# power.net
KiCad netlist of a schematic drawn in Altium Designer
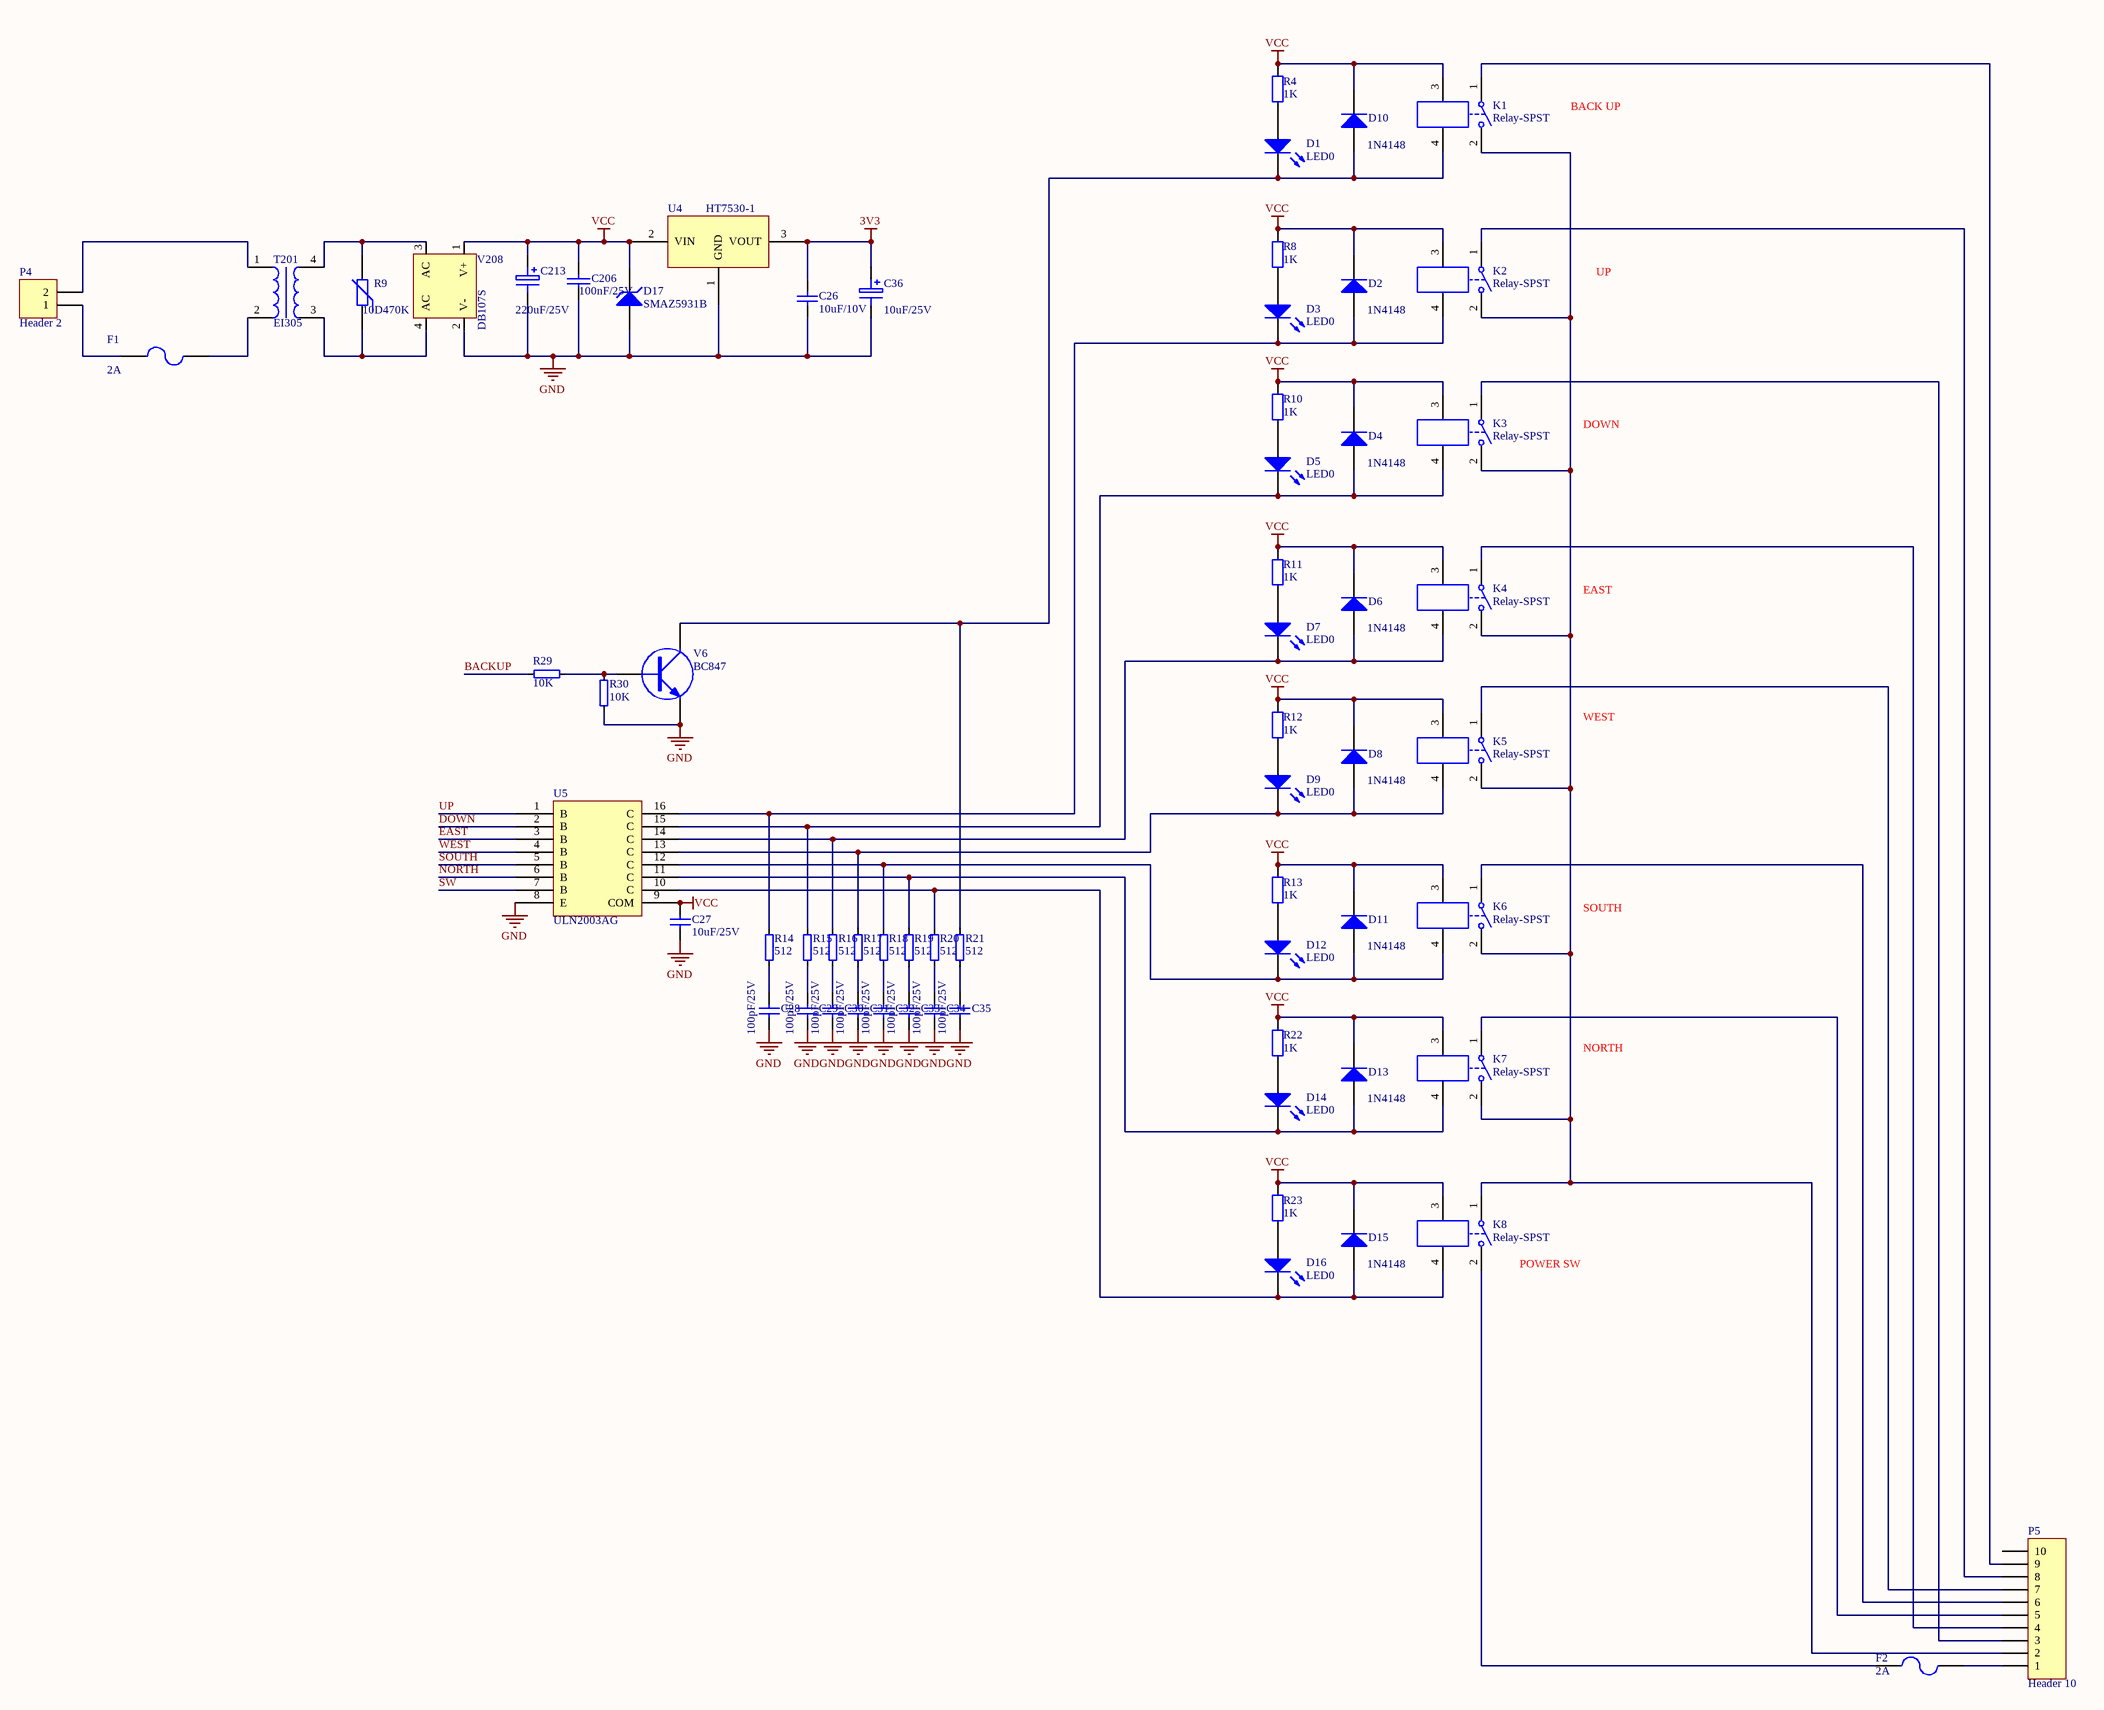
[diagram p0: power.SchDoc]

(export (version "E")
  (design (tool "Eeschema 10.0.6"))
  (components
    (comp (ref "C26")
      (value "10uF/10V")
      (footprint "0603C")
      (description "Capacitor")
      (fields (field (name "PUBLISHER") "Altium Limited"))
      (libsource (lib "Miscellaneous Devices") (part "Cap"))
    )
    (comp (ref "C27")
      (value "10uF/25V")
      (description "Capacitor")
      (fields (field (name "PUBLISHER") "Altium Limited"))
      (libsource (lib "Miscellaneous Devices") (part "Cap"))
    )
    (comp (ref "C28")
      (value "100pF/25V")
      (description "Capacitor")
      (fields (field (name "PUBLISHER") "Altium Limited"))
      (libsource (lib "Miscellaneous Devices") (part "Cap"))
    )
    (comp (ref "C29")
      (value "100pF/25V")
      (description "Capacitor")
      (fields (field (name "PUBLISHER") "Altium Limited"))
      (libsource (lib "Miscellaneous Devices") (part "Cap"))
    )
    (comp (ref "C30")
      (value "100pF/25V")
      (description "Capacitor")
      (fields (field (name "PUBLISHER") "Altium Limited"))
      (libsource (lib "Miscellaneous Devices") (part "Cap"))
    )
    (comp (ref "C31")
      (value "100pF/25V")
      (description "Capacitor")
      (fields (field (name "PUBLISHER") "Altium Limited"))
      (libsource (lib "Miscellaneous Devices") (part "Cap"))
    )
    (comp (ref "C32")
      (value "100pF/25V")
      (description "Capacitor")
      (fields (field (name "PUBLISHER") "Altium Limited"))
      (libsource (lib "Miscellaneous Devices") (part "Cap"))
    )
    (comp (ref "C33")
      (value "100pF/25V")
      (description "Capacitor")
      (fields (field (name "PUBLISHER") "Altium Limited"))
      (libsource (lib "Miscellaneous Devices") (part "Cap"))
    )
    (comp (ref "C34")
      (value "100pF/25V")
      (description "Capacitor")
      (fields (field (name "PUBLISHER") "Altium Limited"))
      (libsource (lib "Miscellaneous Devices") (part "Cap"))
    )
    (comp (ref "C35")
      (value "100pF/25V")
      (description "Capacitor")
      (fields (field (name "PUBLISHER") "Altium Limited"))
      (libsource (lib "Miscellaneous Devices") (part "Cap"))
    )
    (comp (ref "C36")
      (value "10uF/25V")
      (description "Electrolytic Capacitor")
      (libsource (lib "*") (part "ELECTRO1"))
    )
    (comp (ref "C206") (value "100nF/25V") (description "Capacitor") (libsource (lib "*") (part "CAP")))
    (comp (ref "C213")
      (value "220uF/25V")
      (description "Electrolytic Capacitor")
      (libsource (lib "*") (part "ELECTRO1"))
    )
    (comp (ref "D1")
      (value "LED0")
      (footprint "0603led")
      (description "Typical INFRARED GaAs LED")
      (fields (field (name "PUBLISHER") "Altium Limited"))
      (libsource (lib "Miscellaneous Devices") (part "LED0"))
    )
    (comp (ref "D2")
      (value "1N4148")
      (footprint "2017MAIN - BOM:SMD-D")
      (description "Default Diode")
      (fields (field (name "PUBLISHER") "Altium Limited"))
      (libsource (lib "Miscellaneous Devices") (part "Diode"))
    )
    (comp (ref "D3")
      (value "LED0")
      (footprint "0603led")
      (description "Typical INFRARED GaAs LED")
      (fields (field (name "PUBLISHER") "Altium Limited"))
      (libsource (lib "Miscellaneous Devices") (part "LED0"))
    )
    (comp (ref "D4")
      (value "1N4148")
      (footprint "2017MAIN - BOM:SMD-D")
      (description "Default Diode")
      (fields (field (name "PUBLISHER") "Altium Limited"))
      (libsource (lib "Miscellaneous Devices") (part "Diode"))
    )
    (comp (ref "D5")
      (value "LED0")
      (footprint "0603led")
      (description "Typical INFRARED GaAs LED")
      (fields (field (name "PUBLISHER") "Altium Limited"))
      (libsource (lib "Miscellaneous Devices") (part "LED0"))
    )
    (comp (ref "D6")
      (value "1N4148")
      (footprint "2017MAIN - BOM:SMD-D")
      (description "Default Diode")
      (fields (field (name "PUBLISHER") "Altium Limited"))
      (libsource (lib "Miscellaneous Devices") (part "Diode"))
    )
    (comp (ref "D7")
      (value "LED0")
      (footprint "0603led")
      (description "Typical INFRARED GaAs LED")
      (fields (field (name "PUBLISHER") "Altium Limited"))
      (libsource (lib "Miscellaneous Devices") (part "LED0"))
    )
    (comp (ref "D8")
      (value "1N4148")
      (footprint "2017MAIN - BOM:SMD-D")
      (description "Default Diode")
      (fields (field (name "PUBLISHER") "Altium Limited"))
      (libsource (lib "Miscellaneous Devices") (part "Diode"))
    )
    (comp (ref "D9")
      (value "LED0")
      (footprint "0603led")
      (description "Typical INFRARED GaAs LED")
      (fields (field (name "PUBLISHER") "Altium Limited"))
      (libsource (lib "Miscellaneous Devices") (part "LED0"))
    )
    (comp (ref "D10")
      (value "1N4148")
      (footprint "2017MAIN - BOM:SMD-D")
      (description "Default Diode")
      (fields (field (name "PUBLISHER") "Altium Limited"))
      (libsource (lib "Miscellaneous Devices") (part "Diode"))
    )
    (comp (ref "D11")
      (value "1N4148")
      (footprint "2017MAIN - BOM:SMD-D")
      (description "Default Diode")
      (fields (field (name "PUBLISHER") "Altium Limited"))
      (libsource (lib "Miscellaneous Devices") (part "Diode"))
    )
    (comp (ref "D12")
      (value "LED0")
      (footprint "0603led")
      (description "Typical INFRARED GaAs LED")
      (fields (field (name "PUBLISHER") "Altium Limited"))
      (libsource (lib "Miscellaneous Devices") (part "LED0"))
    )
    (comp (ref "D13")
      (value "1N4148")
      (footprint "2017MAIN - BOM:SMD-D")
      (description "Default Diode")
      (fields (field (name "PUBLISHER") "Altium Limited"))
      (libsource (lib "Miscellaneous Devices") (part "Diode"))
    )
    (comp (ref "D14")
      (value "LED0")
      (footprint "0603led")
      (description "Typical INFRARED GaAs LED")
      (fields (field (name "PUBLISHER") "Altium Limited"))
      (libsource (lib "Miscellaneous Devices") (part "LED0"))
    )
    (comp (ref "D15")
      (value "1N4148")
      (footprint "2017MAIN - BOM:SMD-D")
      (description "Default Diode")
      (fields (field (name "PUBLISHER") "Altium Limited"))
      (libsource (lib "Miscellaneous Devices") (part "Diode"))
    )
    (comp (ref "D16")
      (value "LED0")
      (footprint "0603led")
      (description "Typical INFRARED GaAs LED")
      (fields (field (name "PUBLISHER") "Altium Limited"))
      (libsource (lib "Miscellaneous Devices") (part "LED0"))
    )
    (comp (ref "D17")
      (value "SMAZ5931B")
      (footprint "SMA")
      (description "Zener Diode")
      (fields (field (name "PUBLISHER") "Altium Limited"))
      (libsource (lib "Miscellaneous Devices") (part "D Zener"))
    )
    (comp (ref "F1")
      (value "2A")
      (footprint "2017MAIN - BOM:FU")
      (description "Fuse")
      (fields (field (name "PUBLISHER") "Altium Limited"))
      (libsource (lib "Miscellaneous Devices") (part "Fuse 2"))
    )
    (comp (ref "F2")
      (value "2A")
      (footprint "2017MAIN - BOM:FU")
      (description "Fuse")
      (fields (field (name "PUBLISHER") "Altium Limited"))
      (libsource (lib "Miscellaneous Devices") (part "Fuse 2"))
    )
    (comp (ref "K1")
      (value "Relay-SPST")
      (footprint "2017MAIN - BOM:KKK")
      (description "Single-Pole Single-Throw Relay")
      (fields (field (name "PUBLISHER") "Altium Limited"))
      (libsource (lib "Miscellaneous Devices") (part "Relay-SPST"))
    )
    (comp (ref "K2")
      (value "Relay-SPST")
      (footprint "2017MAIN - BOM:KKK")
      (description "Single-Pole Single-Throw Relay")
      (fields (field (name "PUBLISHER") "Altium Limited"))
      (libsource (lib "Miscellaneous Devices") (part "Relay-SPST"))
    )
    (comp (ref "K3")
      (value "Relay-SPST")
      (footprint "2017MAIN - BOM:KKK")
      (description "Single-Pole Single-Throw Relay")
      (fields (field (name "PUBLISHER") "Altium Limited"))
      (libsource (lib "Miscellaneous Devices") (part "Relay-SPST"))
    )
    (comp (ref "K4")
      (value "Relay-SPST")
      (footprint "2017MAIN - BOM:KKK")
      (description "Single-Pole Single-Throw Relay")
      (fields (field (name "PUBLISHER") "Altium Limited"))
      (libsource (lib "Miscellaneous Devices") (part "Relay-SPST"))
    )
    (comp (ref "K5")
      (value "Relay-SPST")
      (footprint "2017MAIN - BOM:KKK")
      (description "Single-Pole Single-Throw Relay")
      (fields (field (name "PUBLISHER") "Altium Limited"))
      (libsource (lib "Miscellaneous Devices") (part "Relay-SPST"))
    )
    (comp (ref "K6")
      (value "Relay-SPST")
      (footprint "2017MAIN - BOM:KKK")
      (description "Single-Pole Single-Throw Relay")
      (fields (field (name "PUBLISHER") "Altium Limited"))
      (libsource (lib "Miscellaneous Devices") (part "Relay-SPST"))
    )
    (comp (ref "K7")
      (value "Relay-SPST")
      (footprint "2017MAIN - BOM:KKK")
      (description "Single-Pole Single-Throw Relay")
      (fields (field (name "PUBLISHER") "Altium Limited"))
      (libsource (lib "Miscellaneous Devices") (part "Relay-SPST"))
    )
    (comp (ref "K8")
      (value "Relay-SPST")
      (footprint "2017MAIN - BOM:KKK")
      (description "Single-Pole Single-Throw Relay")
      (fields (field (name "PUBLISHER") "Altium Limited"))
      (libsource (lib "Miscellaneous Devices") (part "Relay-SPST"))
    )
    (comp (ref "P4")
      (value "Header 2")
      (footprint "2017MAIN - BOM:CH022")
      (description "Header, 2-Pin")
      (fields (field (name "PUBLISHER") "Altium Limited"))
      (libsource (lib "Miscellaneous Connectors") (part "Header 2"))
    )
    (comp (ref "P5")
      (value "Header 10")
      (footprint "2017MAIN - BOM:CN10")
      (description "Header, 10-Pin")
      (fields (field (name "PUBLISHER") "Altium Limited"))
      (libsource (lib "Miscellaneous Connectors") (part "Header 10"))
    )
    (comp (ref "R4")
      (value "1K")
      (footprint "0603R")
      (description "Resistor")
      (fields (field (name "PUBLISHER") "Altium Limited"))
      (libsource (lib "Miscellaneous Devices") (part "Res2"))
    )
    (comp (ref "R8")
      (value "1K")
      (footprint "0603R")
      (description "Resistor")
      (fields (field (name "PUBLISHER") "Altium Limited"))
      (libsource (lib "Miscellaneous Devices") (part "Res2"))
    )
    (comp (ref "R9")
      (value "10D470K")
      (description "Varistor (Voltage-Sensitive Resistor)")
      (fields (field (name "PUBLISHER") "Altium Limited"))
      (libsource (lib "Miscellaneous Devices") (part "Res Varistor"))
    )
    (comp (ref "R10")
      (value "1K")
      (footprint "0603R")
      (description "Resistor")
      (fields (field (name "PUBLISHER") "Altium Limited"))
      (libsource (lib "Miscellaneous Devices") (part "Res2"))
    )
    (comp (ref "R11")
      (value "1K")
      (footprint "0603R")
      (description "Resistor")
      (fields (field (name "PUBLISHER") "Altium Limited"))
      (libsource (lib "Miscellaneous Devices") (part "Res2"))
    )
    (comp (ref "R12")
      (value "1K")
      (footprint "0603R")
      (description "Resistor")
      (fields (field (name "PUBLISHER") "Altium Limited"))
      (libsource (lib "Miscellaneous Devices") (part "Res2"))
    )
    (comp (ref "R13")
      (value "1K")
      (footprint "0603R")
      (description "Resistor")
      (fields (field (name "PUBLISHER") "Altium Limited"))
      (libsource (lib "Miscellaneous Devices") (part "Res2"))
    )
    (comp (ref "R14") (value "512") (footprint "0603R") (libsource (lib "*") (part "RES2")))
    (comp (ref "R15") (value "512") (footprint "0603R") (libsource (lib "*") (part "RES2")))
    (comp (ref "R16") (value "512") (footprint "0603R") (libsource (lib "*") (part "RES2")))
    (comp (ref "R17") (value "512") (footprint "0603R") (libsource (lib "*") (part "RES2")))
    (comp (ref "R18") (value "512") (footprint "0603R") (libsource (lib "*") (part "RES2")))
    (comp (ref "R19") (value "512") (footprint "0603R") (libsource (lib "*") (part "RES2")))
    (comp (ref "R20") (value "512") (footprint "0603R") (libsource (lib "*") (part "RES2")))
    (comp (ref "R21") (value "512") (footprint "0603R") (libsource (lib "*") (part "RES2")))
    (comp (ref "R22")
      (value "1K")
      (footprint "0603R")
      (description "Resistor")
      (fields (field (name "PUBLISHER") "Altium Limited"))
      (libsource (lib "Miscellaneous Devices") (part "Res2"))
    )
    (comp (ref "R23")
      (value "1K")
      (footprint "0603R")
      (description "Resistor")
      (fields (field (name "PUBLISHER") "Altium Limited"))
      (libsource (lib "Miscellaneous Devices") (part "Res2"))
    )
    (comp (ref "R29") (value "10K") (footprint "0603R") (libsource (lib "*") (part "RES2")))
    (comp (ref "R30") (value "10K") (footprint "0603R") (libsource (lib "*") (part "RES2")))
    (comp (ref "T201") (value "EI305") (footprint "2017MAIN - BOM:T01") (libsource (lib "*") (part "EI305")))
    (comp (ref "U4") (value "HT7530-1") (libsource (lib "Schlib_20110825") (part "HT7533-1")))
    (comp (ref "U5") (value "ULN2003AG") (libsource (lib "Schlib_20110825") (part "ULN2003AG")))
    (comp (ref "V6")
      (value "BC847")
      (footprint "SOT-23")
      (description "NPN Transistor")
      (libsource (lib "*") (part "NPN"))
    )
    (comp (ref "V208")
      (value "DB107S")
      (footprint "BRIDGE")
      (description "Diode Bridge")
      (libsource (lib "*") (part "BRIDGE2"))
    )
  )
  (nets
    (net (code "1") (name "/BACKUP") (class "Default")
      (node (ref "R29") (pin "1") (pinfunction "1_1") (pintype "passive"))
    )
    (net (code "2") (name "/DOWN") (class "Default")
      (node (ref "U5") (pin "2") (pinfunction "B_2") (pintype "passive"))
    )
    (net (code "3") (name "/EAST") (class "Default")
      (node (ref "U5") (pin "3") (pinfunction "B_3") (pintype "passive"))
    )
    (net (code "4") (name "/NORTH") (class "Default")
      (node (ref "U5") (pin "6") (pinfunction "B_6") (pintype "passive"))
    )
    (net (code "5") (name "/SOUTH") (class "Default")
      (node (ref "U5") (pin "5") (pinfunction "B_5") (pintype "passive"))
    )
    (net (code "6") (name "/SW") (class "Default")
      (node (ref "U5") (pin "7") (pinfunction "B_7") (pintype "passive"))
    )
    (net (code "7") (name "/UP") (class "Default")
      (node (ref "U5") (pin "1") (pinfunction "B_1") (pintype "passive"))
    )
    (net (code "8") (name "/WEST") (class "Default")
      (node (ref "U5") (pin "4") (pinfunction "B_4") (pintype "passive"))
    )
    (net (code "9") (name "3V3") (class "Default")
      (node (ref "C26") (pin "1") (pinfunction "1_1") (pintype "passive"))
      (node (ref "C36") (pin "1") (pinfunction "1_1") (pintype "passive"))
      (node (ref "U4") (pin "3") (pinfunction "VOUT_3") (pintype "passive"))
    )
    (net (code "10") (name "GND") (class "Default")
      (node (ref "C206") (pin "2") (pinfunction "2_2") (pintype "passive"))
      (node (ref "C213") (pin "2") (pinfunction "2_2") (pintype "passive"))
      (node (ref "C26") (pin "2") (pinfunction "2_2") (pintype "passive"))
      (node (ref "C27") (pin "2") (pinfunction "2_2") (pintype "passive"))
      (node (ref "C28") (pin "2") (pinfunction "2_2") (pintype "passive"))
      (node (ref "C29") (pin "2") (pinfunction "2_2") (pintype "passive"))
      (node (ref "C30") (pin "2") (pinfunction "2_2") (pintype "passive"))
      (node (ref "C31") (pin "2") (pinfunction "2_2") (pintype "passive"))
      (node (ref "C32") (pin "2") (pinfunction "2_2") (pintype "passive"))
      (node (ref "C33") (pin "2") (pinfunction "2_2") (pintype "passive"))
      (node (ref "C34") (pin "2") (pinfunction "2_2") (pintype "passive"))
      (node (ref "C35") (pin "2") (pinfunction "2_2") (pintype "passive"))
      (node (ref "C36") (pin "2") (pinfunction "2_2") (pintype "passive"))
      (node (ref "D17") (pin "1") (pinfunction "A_1") (pintype "passive"))
      (node (ref "R30") (pin "2") (pinfunction "2_2") (pintype "passive"))
      (node (ref "U4") (pin "1") (pinfunction "GND_1") (pintype "passive"))
      (node (ref "U5") (pin "8") (pinfunction "E_8") (pintype "passive"))
      (node (ref "V208") (pin "2") (pinfunction "V-_2") (pintype "passive"))
      (node (ref "V6") (pin "2") (pinfunction "E_2") (pintype "passive"))
    )
    (net (code "11") (name "Net-(C28-Pad1)") (class "Default")
      (node (ref "C28") (pin "1") (pinfunction "1_1") (pintype "passive"))
      (node (ref "R14") (pin "2") (pinfunction "2_2") (pintype "passive"))
    )
    (net (code "12") (name "Net-(C29-Pad1)") (class "Default")
      (node (ref "C29") (pin "1") (pinfunction "1_1") (pintype "passive"))
      (node (ref "R15") (pin "2") (pinfunction "2_2") (pintype "passive"))
    )
    (net (code "13") (name "Net-(C30-Pad1)") (class "Default")
      (node (ref "C30") (pin "1") (pinfunction "1_1") (pintype "passive"))
      (node (ref "R16") (pin "2") (pinfunction "2_2") (pintype "passive"))
    )
    (net (code "14") (name "Net-(C31-Pad1)") (class "Default")
      (node (ref "C31") (pin "1") (pinfunction "1_1") (pintype "passive"))
      (node (ref "R17") (pin "2") (pinfunction "2_2") (pintype "passive"))
    )
    (net (code "15") (name "Net-(C32-Pad1)") (class "Default")
      (node (ref "C32") (pin "1") (pinfunction "1_1") (pintype "passive"))
      (node (ref "R18") (pin "2") (pinfunction "2_2") (pintype "passive"))
    )
    (net (code "16") (name "Net-(C33-Pad1)") (class "Default")
      (node (ref "C33") (pin "1") (pinfunction "1_1") (pintype "passive"))
      (node (ref "R19") (pin "2") (pinfunction "2_2") (pintype "passive"))
    )
    (net (code "17") (name "Net-(C34-Pad1)") (class "Default")
      (node (ref "C34") (pin "1") (pinfunction "1_1") (pintype "passive"))
      (node (ref "R20") (pin "2") (pinfunction "2_2") (pintype "passive"))
    )
    (net (code "18") (name "Net-(C35-Pad1)") (class "Default")
      (node (ref "C35") (pin "1") (pinfunction "1_1") (pintype "passive"))
      (node (ref "R21") (pin "2") (pinfunction "2_2") (pintype "passive"))
    )
    (net (code "19") (name "Net-(D1-A)") (class "Default")
      (node (ref "D1") (pin "1") (pinfunction "A_1") (pintype "passive"))
      (node (ref "R4") (pin "1") (pinfunction "1_1") (pintype "passive"))
    )
    (net (code "20") (name "Net-(D1-K)") (class "Default")
      (node (ref "D1") (pin "2") (pinfunction "K_2") (pintype "passive"))
      (node (ref "D10") (pin "1") (pinfunction "A_1") (pintype "passive"))
      (node (ref "K1") (pin "4") (pinfunction "4_4") (pintype "passive"))
      (node (ref "R21") (pin "1") (pinfunction "1_1") (pintype "passive"))
      (node (ref "V6") (pin "3") (pinfunction "C_3") (pintype "passive"))
    )
    (net (code "21") (name "Net-(D2-A)") (class "Default")
      (node (ref "D2") (pin "1") (pinfunction "A_1") (pintype "passive"))
      (node (ref "D3") (pin "2") (pinfunction "K_2") (pintype "passive"))
      (node (ref "K2") (pin "4") (pinfunction "4_4") (pintype "passive"))
      (node (ref "R14") (pin "1") (pinfunction "1_1") (pintype "passive"))
      (node (ref "U5") (pin "16") (pinfunction "C_16") (pintype "passive"))
    )
    (net (code "22") (name "Net-(D3-A)") (class "Default")
      (node (ref "D3") (pin "1") (pinfunction "A_1") (pintype "passive"))
      (node (ref "R8") (pin "1") (pinfunction "1_1") (pintype "passive"))
    )
    (net (code "23") (name "Net-(D4-A)") (class "Default")
      (node (ref "D4") (pin "1") (pinfunction "A_1") (pintype "passive"))
      (node (ref "D5") (pin "2") (pinfunction "K_2") (pintype "passive"))
      (node (ref "K3") (pin "4") (pinfunction "4_4") (pintype "passive"))
      (node (ref "R15") (pin "1") (pinfunction "1_1") (pintype "passive"))
      (node (ref "U5") (pin "15") (pinfunction "C_15") (pintype "passive"))
    )
    (net (code "24") (name "Net-(D5-A)") (class "Default")
      (node (ref "D5") (pin "1") (pinfunction "A_1") (pintype "passive"))
      (node (ref "R10") (pin "1") (pinfunction "1_1") (pintype "passive"))
    )
    (net (code "25") (name "Net-(D6-A)") (class "Default")
      (node (ref "D6") (pin "1") (pinfunction "A_1") (pintype "passive"))
      (node (ref "D7") (pin "2") (pinfunction "K_2") (pintype "passive"))
      (node (ref "K4") (pin "4") (pinfunction "4_4") (pintype "passive"))
      (node (ref "R16") (pin "1") (pinfunction "1_1") (pintype "passive"))
      (node (ref "U5") (pin "14") (pinfunction "C_14") (pintype "passive"))
    )
    (net (code "26") (name "Net-(D7-A)") (class "Default")
      (node (ref "D7") (pin "1") (pinfunction "A_1") (pintype "passive"))
      (node (ref "R11") (pin "1") (pinfunction "1_1") (pintype "passive"))
    )
    (net (code "27") (name "Net-(D8-A)") (class "Default")
      (node (ref "D8") (pin "1") (pinfunction "A_1") (pintype "passive"))
      (node (ref "D9") (pin "2") (pinfunction "K_2") (pintype "passive"))
      (node (ref "K5") (pin "4") (pinfunction "4_4") (pintype "passive"))
      (node (ref "R17") (pin "1") (pinfunction "1_1") (pintype "passive"))
      (node (ref "U5") (pin "13") (pinfunction "C_13") (pintype "passive"))
    )
    (net (code "28") (name "Net-(D9-A)") (class "Default")
      (node (ref "D9") (pin "1") (pinfunction "A_1") (pintype "passive"))
      (node (ref "R12") (pin "1") (pinfunction "1_1") (pintype "passive"))
    )
    (net (code "29") (name "Net-(D11-A)") (class "Default")
      (node (ref "D11") (pin "1") (pinfunction "A_1") (pintype "passive"))
      (node (ref "D12") (pin "2") (pinfunction "K_2") (pintype "passive"))
      (node (ref "K6") (pin "4") (pinfunction "4_4") (pintype "passive"))
      (node (ref "R18") (pin "1") (pinfunction "1_1") (pintype "passive"))
      (node (ref "U5") (pin "12") (pinfunction "C_12") (pintype "passive"))
    )
    (net (code "30") (name "Net-(D12-A)") (class "Default")
      (node (ref "D12") (pin "1") (pinfunction "A_1") (pintype "passive"))
      (node (ref "R13") (pin "1") (pinfunction "1_1") (pintype "passive"))
    )
    (net (code "31") (name "Net-(D13-A)") (class "Default")
      (node (ref "D13") (pin "1") (pinfunction "A_1") (pintype "passive"))
      (node (ref "D14") (pin "2") (pinfunction "K_2") (pintype "passive"))
      (node (ref "K7") (pin "4") (pinfunction "4_4") (pintype "passive"))
      (node (ref "R19") (pin "1") (pinfunction "1_1") (pintype "passive"))
      (node (ref "U5") (pin "11") (pinfunction "C_11") (pintype "passive"))
    )
    (net (code "32") (name "Net-(D14-A)") (class "Default")
      (node (ref "D14") (pin "1") (pinfunction "A_1") (pintype "passive"))
      (node (ref "R22") (pin "1") (pinfunction "1_1") (pintype "passive"))
    )
    (net (code "33") (name "Net-(D15-A)") (class "Default")
      (node (ref "D15") (pin "1") (pinfunction "A_1") (pintype "passive"))
      (node (ref "D16") (pin "2") (pinfunction "K_2") (pintype "passive"))
      (node (ref "K8") (pin "4") (pinfunction "4_4") (pintype "passive"))
      (node (ref "R20") (pin "1") (pinfunction "1_1") (pintype "passive"))
      (node (ref "U5") (pin "10") (pinfunction "C_10") (pintype "passive"))
    )
    (net (code "34") (name "Net-(D16-A)") (class "Default")
      (node (ref "D16") (pin "1") (pinfunction "A_1") (pintype "passive"))
      (node (ref "R23") (pin "1") (pinfunction "1_1") (pintype "passive"))
    )
    (net (code "35") (name "Net-(F1-Pad1)") (class "Default")
      (node (ref "F1") (pin "1") (pinfunction "1_1") (pintype "passive"))
      (node (ref "P4") (pin "1") (pinfunction "1_1") (pintype "passive"))
    )
    (net (code "36") (name "Net-(F1-Pad2)") (class "Default")
      (node (ref "F1") (pin "2") (pinfunction "2_2") (pintype "passive"))
      (node (ref "T201") (pin "2") (pinfunction "2_2") (pintype "passive"))
    )
    (net (code "37") (name "Net-(F2-Pad1)") (class "Default")
      (node (ref "F2") (pin "1") (pinfunction "1_1") (pintype "passive"))
      (node (ref "K8") (pin "2") (pinfunction "2_2") (pintype "passive"))
    )
    (net (code "38") (name "Net-(F2-Pad2)") (class "Default")
      (node (ref "F2") (pin "2") (pinfunction "2_2") (pintype "passive"))
      (node (ref "P5") (pin "1") (pinfunction "1_1") (pintype "passive"))
    )
    (net (code "39") (name "Net-(K1-Pad1)") (class "Default")
      (node (ref "K1") (pin "1") (pinfunction "1_1") (pintype "passive"))
      (node (ref "P5") (pin "9") (pinfunction "9_9") (pintype "passive"))
    )
    (net (code "40") (name "Net-(K1-Pad2)") (class "Default")
      (node (ref "K1") (pin "2") (pinfunction "2_2") (pintype "passive"))
      (node (ref "K2") (pin "2") (pinfunction "2_2") (pintype "passive"))
      (node (ref "K3") (pin "2") (pinfunction "2_2") (pintype "passive"))
      (node (ref "K4") (pin "2") (pinfunction "2_2") (pintype "passive"))
      (node (ref "K5") (pin "2") (pinfunction "2_2") (pintype "passive"))
      (node (ref "K6") (pin "2") (pinfunction "2_2") (pintype "passive"))
      (node (ref "K7") (pin "2") (pinfunction "2_2") (pintype "passive"))
      (node (ref "K8") (pin "1") (pinfunction "1_1") (pintype "passive"))
      (node (ref "P5") (pin "2") (pinfunction "2_2") (pintype "passive"))
    )
    (net (code "41") (name "Net-(K2-Pad1)") (class "Default")
      (node (ref "K2") (pin "1") (pinfunction "1_1") (pintype "passive"))
      (node (ref "P5") (pin "8") (pinfunction "8_8") (pintype "passive"))
    )
    (net (code "42") (name "Net-(K3-Pad1)") (class "Default")
      (node (ref "K3") (pin "1") (pinfunction "1_1") (pintype "passive"))
      (node (ref "P5") (pin "3") (pinfunction "3_3") (pintype "passive"))
    )
    (net (code "43") (name "Net-(K4-Pad1)") (class "Default")
      (node (ref "K4") (pin "1") (pinfunction "1_1") (pintype "passive"))
      (node (ref "P5") (pin "4") (pinfunction "4_4") (pintype "passive"))
    )
    (net (code "44") (name "Net-(K5-Pad1)") (class "Default")
      (node (ref "K5") (pin "1") (pinfunction "1_1") (pintype "passive"))
      (node (ref "P5") (pin "7") (pinfunction "7_7") (pintype "passive"))
    )
    (net (code "45") (name "Net-(K6-Pad1)") (class "Default")
      (node (ref "K6") (pin "1") (pinfunction "1_1") (pintype "passive"))
      (node (ref "P5") (pin "6") (pinfunction "6_6") (pintype "passive"))
    )
    (net (code "46") (name "Net-(K7-Pad1)") (class "Default")
      (node (ref "K7") (pin "1") (pinfunction "1_1") (pintype "passive"))
      (node (ref "P5") (pin "5") (pinfunction "5_5") (pintype "passive"))
    )
    (net (code "47") (name "Net-(P4-Pad2)") (class "Default")
      (node (ref "P4") (pin "2") (pinfunction "2_2") (pintype "passive"))
      (node (ref "T201") (pin "1") (pinfunction "1_1") (pintype "passive"))
    )
    (net (code "48") (name "Net-(R9-Pad1)") (class "Default")
      (node (ref "R9") (pin "1") (pinfunction "1_1") (pintype "passive"))
      (node (ref "T201") (pin "3") (pinfunction "3_3") (pintype "passive"))
      (node (ref "V208") (pin "4") (pinfunction "AC_4") (pintype "passive"))
    )
    (net (code "49") (name "Net-(R9-Pad2)") (class "Default")
      (node (ref "R9") (pin "2") (pinfunction "2_2") (pintype "passive"))
      (node (ref "T201") (pin "4") (pinfunction "4_4") (pintype "passive"))
      (node (ref "V208") (pin "3") (pinfunction "AC_3") (pintype "passive"))
    )
    (net (code "50") (name "Net-(V6-B)") (class "Default")
      (node (ref "R29") (pin "2") (pinfunction "2_2") (pintype "passive"))
      (node (ref "R30") (pin "1") (pinfunction "1_1") (pintype "passive"))
      (node (ref "V6") (pin "1") (pinfunction "B_1") (pintype "passive"))
    )
    (net (code "51") (name "VCC") (class "Default")
      (node (ref "C206") (pin "1") (pinfunction "1_1") (pintype "passive"))
      (node (ref "C213") (pin "1") (pinfunction "1_1") (pintype "passive"))
      (node (ref "C27") (pin "1") (pinfunction "1_1") (pintype "passive"))
      (node (ref "D10") (pin "2") (pinfunction "K_2") (pintype "passive"))
      (node (ref "D11") (pin "2") (pinfunction "K_2") (pintype "passive"))
      (node (ref "D13") (pin "2") (pinfunction "K_2") (pintype "passive"))
      (node (ref "D15") (pin "2") (pinfunction "K_2") (pintype "passive"))
      (node (ref "D17") (pin "2") (pinfunction "K_2") (pintype "passive"))
      (node (ref "D2") (pin "2") (pinfunction "K_2") (pintype "passive"))
      (node (ref "D4") (pin "2") (pinfunction "K_2") (pintype "passive"))
      (node (ref "D6") (pin "2") (pinfunction "K_2") (pintype "passive"))
      (node (ref "D8") (pin "2") (pinfunction "K_2") (pintype "passive"))
      (node (ref "K1") (pin "3") (pinfunction "3_3") (pintype "passive"))
      (node (ref "K2") (pin "3") (pinfunction "3_3") (pintype "passive"))
      (node (ref "K3") (pin "3") (pinfunction "3_3") (pintype "passive"))
      (node (ref "K4") (pin "3") (pinfunction "3_3") (pintype "passive"))
      (node (ref "K5") (pin "3") (pinfunction "3_3") (pintype "passive"))
      (node (ref "K6") (pin "3") (pinfunction "3_3") (pintype "passive"))
      (node (ref "K7") (pin "3") (pinfunction "3_3") (pintype "passive"))
      (node (ref "K8") (pin "3") (pinfunction "3_3") (pintype "passive"))
      (node (ref "R10") (pin "2") (pinfunction "2_2") (pintype "passive"))
      (node (ref "R11") (pin "2") (pinfunction "2_2") (pintype "passive"))
      (node (ref "R12") (pin "2") (pinfunction "2_2") (pintype "passive"))
      (node (ref "R13") (pin "2") (pinfunction "2_2") (pintype "passive"))
      (node (ref "R22") (pin "2") (pinfunction "2_2") (pintype "passive"))
      (node (ref "R23") (pin "2") (pinfunction "2_2") (pintype "passive"))
      (node (ref "R4") (pin "2") (pinfunction "2_2") (pintype "passive"))
      (node (ref "R8") (pin "2") (pinfunction "2_2") (pintype "passive"))
      (node (ref "U4") (pin "2") (pinfunction "VIN_2") (pintype "passive"))
      (node (ref "U5") (pin "9") (pinfunction "COM_9") (pintype "passive"))
      (node (ref "V208") (pin "1") (pinfunction "V+_1") (pintype "passive"))
    )
    (net (code "52") (name "unconnected-(P5-Pad10)") (class "Default")
      (node (ref "P5") (pin "10") (pinfunction "10_10") (pintype "passive"))
    )
  )
)
